# LM386AMPLIFIER.net
KiCad netlist of a schematic drawn in Altium Designer
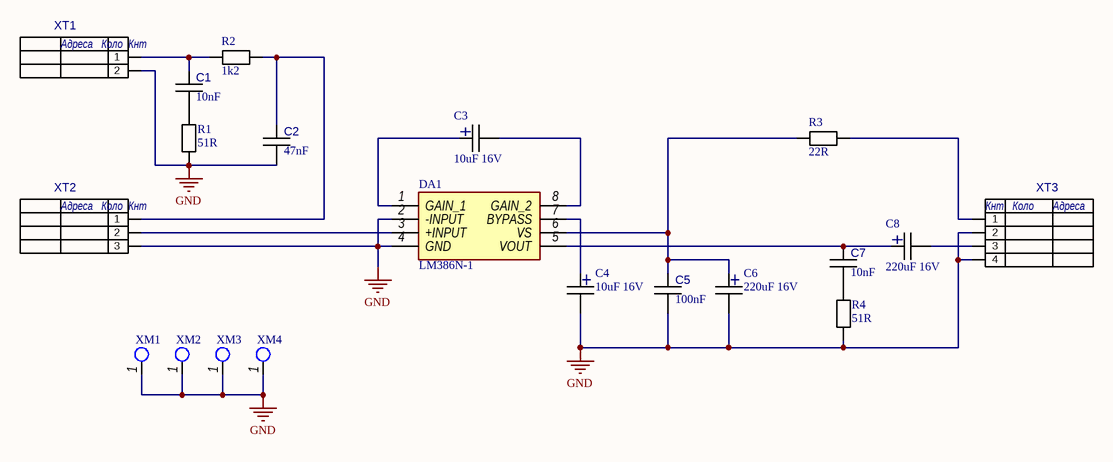
[diagram p0: LM386AMPLIFIER.SchDoc]

(export (version "E")
  (design (tool "Eeschema 10.0.6"))
  (components
    (comp (ref "C1") (value "10nF") (footprint "C1206M") (libsource (lib "MainLib") (part "CAP")))
    (comp (ref "C2") (value "47nF") (footprint "C1206M") (libsource (lib "MainLib") (part "CAP")))
    (comp (ref "C3") (value "10uF 16V") (footprint "D6.3_P2.5") (libsource (lib "MainLib") (part "CAP_EL")))
    (comp (ref "C4") (value "10uF 16V") (footprint "D6.3_P2.5") (libsource (lib "MainLib") (part "CAP_EL")))
    (comp (ref "C5") (value "100nF") (footprint "C1206M") (libsource (lib "MainLib") (part "CAP")))
    (comp (ref "C6") (value "220uF 16V") (footprint "D6.3_P2.5") (libsource (lib "MainLib") (part "CAP_EL")))
    (comp (ref "C7") (value "10nF") (footprint "C1206M") (libsource (lib "MainLib") (part "CAP")))
    (comp (ref "C8") (value "220uF 16V") (footprint "D6.3_P2.5") (libsource (lib "MainLib") (part "CAP_EL")))
    (comp (ref "DA1")
      (value "LM386N-1")
      (footprint "DIP8")
      (description "TEXAS INSTRUMENTS - LM386N-1 - AUDIO POWER AMPLIFIER, CLASS AB, 325mW DIP-8")
      (fields (field (name "MOUSER PART NUMBER") "926-LM386N-1"))
      (libsource (lib "MainLib") (part "LM386N-1"))
    )
    (comp (ref "R1") (value "51R") (footprint "R1206M") (libsource (lib "MainLib") (part "RES")))
    (comp (ref "R2") (value "1k2") (footprint "R1206M") (libsource (lib "MainLib") (part "RES")))
    (comp (ref "R3") (value "22R") (footprint "R1206M") (libsource (lib "MainLib") (part "RES")))
    (comp (ref "R4") (value "51R") (footprint "R1206M") (libsource (lib "MainLib") (part "RES")))
    (comp (ref "XM1") (value "~") (footprint "XM_D6.5mm_d3.6mm") (libsource (lib "MainLib") (part "XM")))
    (comp (ref "XM2") (value "~") (footprint "XM_D6.5mm_d3.6mm") (libsource (lib "MainLib") (part "XM")))
    (comp (ref "XM3") (value "~") (footprint "XM_D6.5mm_d3.6mm") (libsource (lib "MainLib") (part "XM")))
    (comp (ref "XM4") (value "~") (footprint "XM_D6.5mm_d3.6mm") (libsource (lib "MainLib") (part "XM")))
    (comp (ref "XT1") (value "X2") (footprint "WF2") (libsource (lib "MainLib") (part "X2")))
    (comp (ref "XT2") (value "X3") (footprint "WF3") (libsource (lib "MainLib") (part "X3")))
    (comp (ref "XT3") (value "X4") (footprint "WF4") (libsource (lib "MainLib") (part "X4")))
  )
  (nets
    (net (code "1") (name "GND") (class "Default")
      (node (ref "C2") (pin "2") (pintype "passive"))
      (node (ref "C4") (pin "2") (pinfunction "2_2") (pintype "passive"))
      (node (ref "C5") (pin "2") (pintype "passive"))
      (node (ref "C6") (pin "2") (pinfunction "2_2") (pintype "passive"))
      (node (ref "DA1") (pin "2") (pinfunction "-INPUT_2") (pintype "passive"))
      (node (ref "DA1") (pin "4") (pinfunction "GND_4") (pintype "passive"))
      (node (ref "R1") (pin "1") (pintype "passive"))
      (node (ref "R4") (pin "1") (pintype "passive"))
      (node (ref "XM1") (pin "1") (pintype "passive"))
      (node (ref "XM2") (pin "1") (pintype "passive"))
      (node (ref "XM3") (pin "1") (pintype "passive"))
      (node (ref "XM4") (pin "1") (pintype "passive"))
      (node (ref "XT1") (pin "2") (pinfunction "2_2") (pintype "passive"))
      (node (ref "XT2") (pin "3") (pinfunction "3_3") (pintype "passive"))
      (node (ref "XT3") (pin "2") (pinfunction "2_2") (pintype "passive"))
      (node (ref "XT3") (pin "4") (pinfunction "4_4") (pintype "passive"))
    )
    (net (code "2") (name "Net-(C1-Pad1)") (class "Default")
      (node (ref "C1") (pin "1") (pintype "passive"))
      (node (ref "R2") (pin "2") (pintype "passive"))
      (node (ref "XT1") (pin "1") (pinfunction "1_1") (pintype "passive"))
    )
    (net (code "3") (name "Net-(C1-Pad2)") (class "Default")
      (node (ref "C1") (pin "2") (pintype "passive"))
      (node (ref "R1") (pin "2") (pintype "passive"))
    )
    (net (code "4") (name "Net-(C2-Pad1)") (class "Default")
      (node (ref "C2") (pin "1") (pintype "passive"))
      (node (ref "R2") (pin "1") (pintype "passive"))
      (node (ref "XT2") (pin "1") (pinfunction "1_1") (pintype "passive"))
    )
    (net (code "5") (name "Net-(C7-Pad2)") (class "Default")
      (node (ref "C7") (pin "2") (pintype "passive"))
      (node (ref "R4") (pin "2") (pintype "passive"))
    )
    (net (code "6") (name "Net-(C8-Pad2)") (class "Default")
      (node (ref "C8") (pin "2") (pinfunction "2_2") (pintype "passive"))
      (node (ref "XT3") (pin "3") (pinfunction "3_3") (pintype "passive"))
    )
    (net (code "7") (name "Net-(DA1-+INPUT)") (class "Default")
      (node (ref "DA1") (pin "3") (pinfunction "+INPUT_3") (pintype "passive"))
      (node (ref "XT2") (pin "2") (pinfunction "2_2") (pintype "passive"))
    )
    (net (code "8") (name "Net-(DA1-BYPASS)") (class "Default")
      (node (ref "C4") (pin "1") (pinfunction "1_1") (pintype "passive"))
      (node (ref "DA1") (pin "7") (pinfunction "BYPASS_7") (pintype "passive"))
    )
    (net (code "9") (name "Net-(DA1-GAIN_1)") (class "Default")
      (node (ref "C3") (pin "1") (pinfunction "1_1") (pintype "passive"))
      (node (ref "DA1") (pin "1") (pinfunction "GAIN_1_1") (pintype "passive"))
    )
    (net (code "10") (name "Net-(DA1-GAIN_2)") (class "Default")
      (node (ref "C3") (pin "2") (pinfunction "2_2") (pintype "passive"))
      (node (ref "DA1") (pin "8") (pinfunction "GAIN_2_8") (pintype "passive"))
    )
    (net (code "11") (name "Net-(DA1-VOUT)") (class "Default")
      (node (ref "C7") (pin "1") (pintype "passive"))
      (node (ref "C8") (pin "1") (pinfunction "1_1") (pintype "passive"))
      (node (ref "DA1") (pin "5") (pinfunction "VOUT_5") (pintype "passive"))
    )
    (net (code "12") (name "Net-(DA1-VS)") (class "Default")
      (node (ref "C5") (pin "1") (pintype "passive"))
      (node (ref "C6") (pin "1") (pinfunction "1_1") (pintype "passive"))
      (node (ref "DA1") (pin "6") (pinfunction "VS_6") (pintype "passive"))
      (node (ref "R3") (pin "1") (pintype "passive"))
    )
    (net (code "13") (name "Net-(R3-Pad2)") (class "Default")
      (node (ref "R3") (pin "2") (pintype "passive"))
      (node (ref "XT3") (pin "1") (pinfunction "1_1") (pintype "passive"))
    )
  )
)
